# ECU.net
KiCad netlist of a schematic drawn in EAGLE
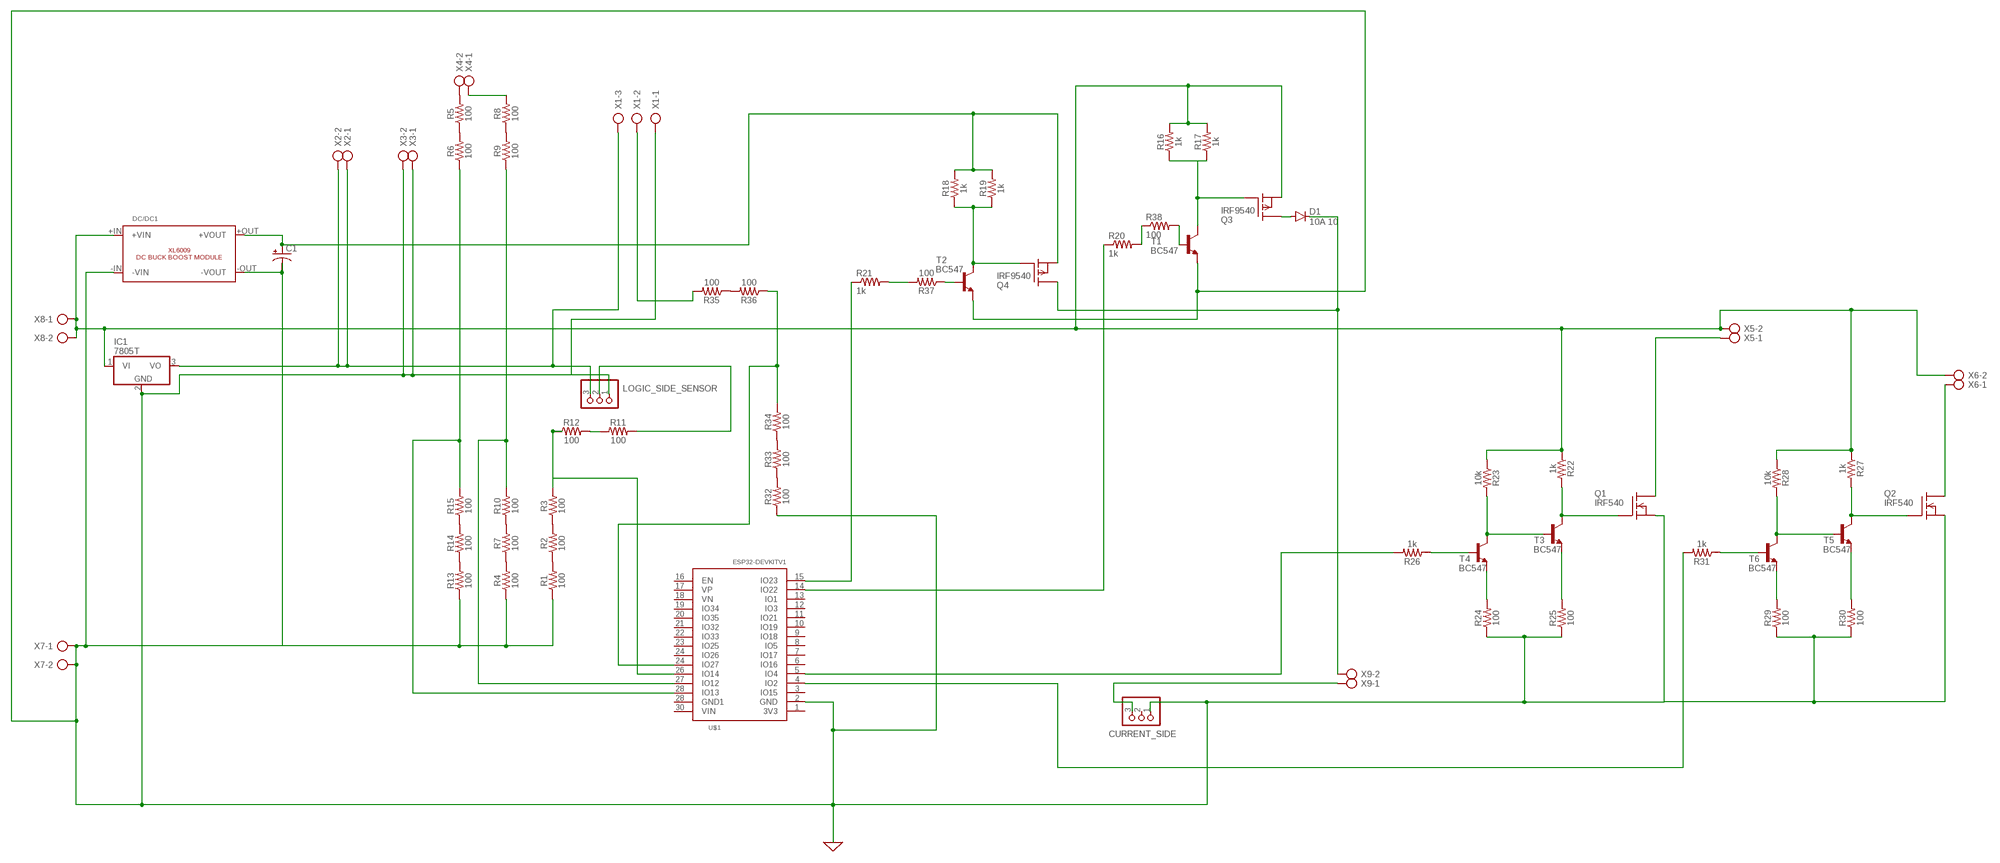
[diagram p0: schematic, sheet 1]

(export (version "E")
  (design (tool "Eeschema 10.0.6"))
  (components
    (comp (ref "C1")
      (value "CPOL-USE7.5-18")
      (footprint "eagle-import:E7,5-18")
      (libsource (lib "eagle-import") (part "CPOL-USE7.5-18"))
    )
    (comp (ref "CURRENT_SIDE")
      (value "PINHD-1X3")
      (footprint "eagle-import:1X03")
      (libsource (lib "eagle-import") (part "PINHD-1X3"))
    )
    (comp (ref "D1")
      (value "10A 10")
      (footprint "eagle-import:DO201-15")
      (libsource (lib "eagle-import") (part "1N5400"))
    )
    (comp (ref "DC/DC1")
      (value "XL6009_DC_BUCK_BOOST_MODULE")
      (footprint "eagle-import:XL6009_DC_BUCK_BOOST_MODULE")
      (libsource (lib "eagle-import") (part "XL6009_DC_BUCK_BOOST_MODULE"))
    )
    (comp (ref "IC1")
      (value "7805T")
      (footprint "eagle-import:TO220H")
      (libsource (lib "eagle-import") (part "78T05"))
    )
    (comp (ref "LOGIC_SIDE_SENSOR")
      (value "PINHD-1X3")
      (footprint "eagle-import:1X03")
      (libsource (lib "eagle-import") (part "PINHD-1X3"))
    )
    (comp (ref "Q1")
      (value "IRF540")
      (footprint "eagle-import:TO220")
      (libsource (lib "eagle-import") (part "IRF540"))
    )
    (comp (ref "Q2")
      (value "IRF540")
      (footprint "eagle-import:TO220")
      (libsource (lib "eagle-import") (part "IRF540"))
    )
    (comp (ref "Q3")
      (value "IRF9540")
      (footprint "eagle-import:TO220")
      (libsource (lib "eagle-import") (part "IRF9530"))
    )
    (comp (ref "Q4")
      (value "IRF9540")
      (footprint "eagle-import:TO220")
      (libsource (lib "eagle-import") (part "IRF9530"))
    )
    (comp (ref "R1")
      (value "100")
      (footprint "eagle-import:AXIAL-0.3")
      (libsource (lib "eagle-import") (part "10OHM-HORIZ-1/4W-1%"))
    )
    (comp (ref "R2")
      (value "100")
      (footprint "eagle-import:AXIAL-0.3")
      (libsource (lib "eagle-import") (part "10OHM-HORIZ-1/4W-1%"))
    )
    (comp (ref "R3")
      (value "100")
      (footprint "eagle-import:AXIAL-0.3")
      (libsource (lib "eagle-import") (part "10OHM-HORIZ-1/4W-1%"))
    )
    (comp (ref "R4")
      (value "100")
      (footprint "eagle-import:AXIAL-0.3")
      (libsource (lib "eagle-import") (part "10OHM-HORIZ-1/4W-1%"))
    )
    (comp (ref "R5")
      (value "100")
      (footprint "eagle-import:AXIAL-0.3")
      (libsource (lib "eagle-import") (part "10OHM-HORIZ-1/4W-1%"))
    )
    (comp (ref "R6")
      (value "100")
      (footprint "eagle-import:AXIAL-0.3")
      (libsource (lib "eagle-import") (part "10OHM-HORIZ-1/4W-1%"))
    )
    (comp (ref "R7")
      (value "100")
      (footprint "eagle-import:AXIAL-0.3")
      (libsource (lib "eagle-import") (part "10OHM-HORIZ-1/4W-1%"))
    )
    (comp (ref "R8")
      (value "100")
      (footprint "eagle-import:AXIAL-0.3")
      (libsource (lib "eagle-import") (part "10OHM-HORIZ-1/4W-1%"))
    )
    (comp (ref "R9")
      (value "100")
      (footprint "eagle-import:AXIAL-0.3")
      (libsource (lib "eagle-import") (part "10OHM-HORIZ-1/4W-1%"))
    )
    (comp (ref "R10")
      (value "100")
      (footprint "eagle-import:AXIAL-0.3")
      (libsource (lib "eagle-import") (part "10OHM-HORIZ-1/4W-1%"))
    )
    (comp (ref "R11")
      (value "100")
      (footprint "eagle-import:AXIAL-0.3")
      (libsource (lib "eagle-import") (part "10OHM-HORIZ-1/4W-1%"))
    )
    (comp (ref "R12")
      (value "100")
      (footprint "eagle-import:AXIAL-0.3")
      (libsource (lib "eagle-import") (part "10OHM-HORIZ-1/4W-1%"))
    )
    (comp (ref "R13")
      (value "100")
      (footprint "eagle-import:AXIAL-0.3")
      (libsource (lib "eagle-import") (part "10OHM-HORIZ-1/4W-1%"))
    )
    (comp (ref "R14")
      (value "100")
      (footprint "eagle-import:AXIAL-0.3")
      (libsource (lib "eagle-import") (part "10OHM-HORIZ-1/4W-1%"))
    )
    (comp (ref "R15")
      (value "100")
      (footprint "eagle-import:AXIAL-0.3")
      (libsource (lib "eagle-import") (part "10OHM-HORIZ-1/4W-1%"))
    )
    (comp (ref "R16")
      (value "1k")
      (footprint "eagle-import:AXIAL-0.3")
      (libsource (lib "eagle-import") (part "1KOHM-HORIZ-1/4W-1%"))
    )
    (comp (ref "R17")
      (value "1k")
      (footprint "eagle-import:AXIAL-0.3")
      (libsource (lib "eagle-import") (part "1KOHM-HORIZ-1/4W-1%"))
    )
    (comp (ref "R18")
      (value "1k")
      (footprint "eagle-import:AXIAL-0.3")
      (libsource (lib "eagle-import") (part "1KOHM-HORIZ-1/4W-1%"))
    )
    (comp (ref "R19")
      (value "1k")
      (footprint "eagle-import:AXIAL-0.3")
      (libsource (lib "eagle-import") (part "1KOHM-HORIZ-1/4W-1%"))
    )
    (comp (ref "R20")
      (value "1k")
      (footprint "eagle-import:0207_12")
      (libsource (lib "eagle-import") (part "R-US_0207/12"))
    )
    (comp (ref "R21")
      (value "1k")
      (footprint "eagle-import:0207_12")
      (libsource (lib "eagle-import") (part "R-US_0207/12"))
    )
    (comp (ref "R22")
      (value "1k")
      (footprint "eagle-import:AXIAL-0.3")
      (libsource (lib "eagle-import") (part "1KOHM-HORIZ-1/4W-1%"))
    )
    (comp (ref "R23")
      (value "10k")
      (footprint "eagle-import:AXIAL-0.3")
      (libsource (lib "eagle-import") (part "1KOHM-HORIZ-1/4W-1%"))
    )
    (comp (ref "R24")
      (value "100")
      (footprint "eagle-import:AXIAL-0.3")
      (libsource (lib "eagle-import") (part "10OHM-HORIZ-1/4W-1%"))
    )
    (comp (ref "R25")
      (value "100")
      (footprint "eagle-import:AXIAL-0.3")
      (libsource (lib "eagle-import") (part "10OHM-HORIZ-1/4W-1%"))
    )
    (comp (ref "R26")
      (value "1k")
      (footprint "eagle-import:AXIAL-0.3")
      (libsource (lib "eagle-import") (part "1KOHM-HORIZ-1/4W-1%"))
    )
    (comp (ref "R27")
      (value "1k")
      (footprint "eagle-import:AXIAL-0.3")
      (libsource (lib "eagle-import") (part "1KOHM-HORIZ-1/4W-1%"))
    )
    (comp (ref "R28")
      (value "10k")
      (footprint "eagle-import:AXIAL-0.3")
      (libsource (lib "eagle-import") (part "1KOHM-HORIZ-1/4W-1%"))
    )
    (comp (ref "R29")
      (value "100")
      (footprint "eagle-import:AXIAL-0.3")
      (libsource (lib "eagle-import") (part "10OHM-HORIZ-1/4W-1%"))
    )
    (comp (ref "R30")
      (value "100")
      (footprint "eagle-import:AXIAL-0.3")
      (libsource (lib "eagle-import") (part "10OHM-HORIZ-1/4W-1%"))
    )
    (comp (ref "R31")
      (value "1k")
      (footprint "eagle-import:AXIAL-0.3")
      (libsource (lib "eagle-import") (part "1KOHM-HORIZ-1/4W-1%"))
    )
    (comp (ref "R32")
      (value "100")
      (footprint "eagle-import:AXIAL-0.3")
      (libsource (lib "eagle-import") (part "10OHM-HORIZ-1/4W-1%"))
    )
    (comp (ref "R33")
      (value "100")
      (footprint "eagle-import:AXIAL-0.3")
      (libsource (lib "eagle-import") (part "10OHM-HORIZ-1/4W-1%"))
    )
    (comp (ref "R34")
      (value "100")
      (footprint "eagle-import:AXIAL-0.3")
      (libsource (lib "eagle-import") (part "10OHM-HORIZ-1/4W-1%"))
    )
    (comp (ref "R35")
      (value "100")
      (footprint "eagle-import:AXIAL-0.3")
      (libsource (lib "eagle-import") (part "10OHM-HORIZ-1/4W-1%"))
    )
    (comp (ref "R36")
      (value "100")
      (footprint "eagle-import:AXIAL-0.3")
      (libsource (lib "eagle-import") (part "10OHM-HORIZ-1/4W-1%"))
    )
    (comp (ref "R37")
      (value "100")
      (footprint "eagle-import:AXIAL-0.3")
      (libsource (lib "eagle-import") (part "10OHM-HORIZ-1/4W-1%"))
    )
    (comp (ref "R38")
      (value "100")
      (footprint "eagle-import:0207_12")
      (libsource (lib "eagle-import") (part "R-US_0207/12"))
    )
    (comp (ref "T1")
      (value "BC547")
      (footprint "eagle-import:TO92")
      (libsource (lib "eagle-import") (part "BC547"))
    )
    (comp (ref "T2")
      (value "BC547")
      (footprint "eagle-import:TO92")
      (libsource (lib "eagle-import") (part "BC547"))
    )
    (comp (ref "T3")
      (value "BC547")
      (footprint "eagle-import:TO92")
      (libsource (lib "eagle-import") (part "BC547"))
    )
    (comp (ref "T4")
      (value "BC547")
      (footprint "eagle-import:TO92")
      (libsource (lib "eagle-import") (part "BC547"))
    )
    (comp (ref "T5")
      (value "BC547")
      (footprint "eagle-import:TO92")
      (libsource (lib "eagle-import") (part "BC547"))
    )
    (comp (ref "T6")
      (value "BC547")
      (footprint "eagle-import:TO92")
      (libsource (lib "eagle-import") (part "BC547"))
    )
    (comp (ref "U$1")
      (value "ESP32DEVKITV1")
      (footprint "eagle-import:ESP32-DEVKITV1")
      (libsource (lib "eagle-import") (part "ESP32DEVKITV1"))
    )
    (comp (ref "X1")
      (value "AK300/3")
      (footprint "eagle-import:AK300_3")
      (libsource (lib "eagle-import") (part "AK300/3"))
    )
    (comp (ref "X2")
      (value "AK300/2")
      (footprint "eagle-import:AK300_2")
      (libsource (lib "eagle-import") (part "AK300/2"))
    )
    (comp (ref "X3")
      (value "AK300/2")
      (footprint "eagle-import:AK300_2")
      (libsource (lib "eagle-import") (part "AK300/2"))
    )
    (comp (ref "X4")
      (value "AK300/2")
      (footprint "eagle-import:AK300_2")
      (libsource (lib "eagle-import") (part "AK300/2"))
    )
    (comp (ref "X5")
      (value "AK300/2")
      (footprint "eagle-import:AK300_2")
      (libsource (lib "eagle-import") (part "AK300/2"))
    )
    (comp (ref "X6")
      (value "AK300/2")
      (footprint "eagle-import:AK300_2")
      (libsource (lib "eagle-import") (part "AK300/2"))
    )
    (comp (ref "X7")
      (value "AK300/2")
      (footprint "eagle-import:AK300_2")
      (libsource (lib "eagle-import") (part "AK300/2"))
    )
    (comp (ref "X8")
      (value "AK300/2")
      (footprint "eagle-import:AK300_2")
      (libsource (lib "eagle-import") (part "AK300/2"))
    )
    (comp (ref "X9")
      (value "AK300/2")
      (footprint "eagle-import:AK300_2")
      (libsource (lib "eagle-import") (part "AK300/2"))
    )
  )
  (nets
    (net (code "1") (name "GND") (class "Default")
      (node (ref "C1") (pin "-") (pinfunction "-_-") (pintype "passive"))
      (node (ref "CURRENT_SIDE") (pin "1") (pinfunction "1_1") (pintype "passive"))
      (node (ref "DC/DC1") (pin "-IN") (pinfunction "-VIN_-IN") (pintype "bidirectional"))
      (node (ref "DC/DC1") (pin "-OUT") (pinfunction "-VOUT_-OUT") (pintype "bidirectional"))
      (node (ref "IC1") (pin "2") (pinfunction "GND_2") (pintype "passive"))
      (node (ref "LOGIC_SIDE_SENSOR") (pin "1") (pinfunction "1_1") (pintype "passive"))
      (node (ref "Q1") (pin "3") (pinfunction "S_3") (pintype "passive"))
      (node (ref "Q2") (pin "3") (pinfunction "S_3") (pintype "passive"))
      (node (ref "R1") (pin "P$1") (pinfunction "1_P$1") (pintype "passive"))
      (node (ref "R13") (pin "P$1") (pinfunction "1_P$1") (pintype "passive"))
      (node (ref "R24") (pin "P$1") (pinfunction "1_P$1") (pintype "passive"))
      (node (ref "R25") (pin "P$1") (pinfunction "1_P$1") (pintype "passive"))
      (node (ref "R29") (pin "P$1") (pinfunction "1_P$1") (pintype "passive"))
      (node (ref "R30") (pin "P$1") (pinfunction "1_P$1") (pintype "passive"))
      (node (ref "R32") (pin "P$1") (pinfunction "1_P$1") (pintype "passive"))
      (node (ref "R4") (pin "P$1") (pinfunction "1_P$1") (pintype "passive"))
      (node (ref "T1") (pin "1") (pinfunction "E_1") (pintype "passive"))
      (node (ref "T2") (pin "1") (pinfunction "E_1") (pintype "passive"))
      (node (ref "U$1") (pin "2") (pinfunction "GND_2") (pintype "bidirectional"))
      (node (ref "X1") (pin "1") (pinfunction "KL_1") (pintype "passive"))
      (node (ref "X3") (pin "1") (pinfunction "KL_1") (pintype "passive"))
      (node (ref "X3") (pin "2") (pinfunction "KL_2") (pintype "passive"))
      (node (ref "X7") (pin "1") (pinfunction "KL_1") (pintype "passive"))
      (node (ref "X7") (pin "2") (pinfunction "KL_2") (pintype "passive"))
    )
    (net (code "2") (name "Net-(DC/DC1-+VIN)") (class "Default")
      (node (ref "DC/DC1") (pin "+IN") (pinfunction "+VIN_+IN") (pintype "bidirectional"))
      (node (ref "IC1") (pin "1") (pinfunction "VI_1") (pintype "input"))
      (node (ref "Q3") (pin "3") (pinfunction "S_3") (pintype "passive"))
      (node (ref "R16") (pin "P$2") (pinfunction "2_P$2") (pintype "passive"))
      (node (ref "R17") (pin "P$2") (pinfunction "2_P$2") (pintype "passive"))
      (node (ref "R22") (pin "P$1") (pinfunction "1_P$1") (pintype "passive"))
      (node (ref "R23") (pin "P$1") (pinfunction "1_P$1") (pintype "passive"))
      (node (ref "R27") (pin "P$1") (pinfunction "1_P$1") (pintype "passive"))
      (node (ref "R28") (pin "P$1") (pinfunction "1_P$1") (pintype "passive"))
      (node (ref "X5") (pin "2") (pinfunction "KL_2") (pintype "passive"))
      (node (ref "X6") (pin "2") (pinfunction "KL_2") (pintype "passive"))
      (node (ref "X8") (pin "1") (pinfunction "KL_1") (pintype "passive"))
      (node (ref "X8") (pin "2") (pinfunction "KL_2") (pintype "passive"))
    )
    (net (code "3") (name "Net-(DC/DC1-+VOUT)") (class "Default")
      (node (ref "C1") (pin "+") (pinfunction "+_+") (pintype "passive"))
      (node (ref "DC/DC1") (pin "+OUT") (pinfunction "+VOUT_+OUT") (pintype "bidirectional"))
      (node (ref "Q4") (pin "3") (pinfunction "S_3") (pintype "passive"))
      (node (ref "R18") (pin "P$2") (pinfunction "2_P$2") (pintype "passive"))
      (node (ref "R19") (pin "P$2") (pinfunction "2_P$2") (pintype "passive"))
    )
    (net (code "4") (name "Net-(IC1-VO)") (class "Default")
      (node (ref "IC1") (pin "3") (pinfunction "VO_3") (pintype "passive"))
      (node (ref "LOGIC_SIDE_SENSOR") (pin "3") (pinfunction "3_3") (pintype "passive"))
      (node (ref "X1") (pin "3") (pinfunction "KL_3") (pintype "passive"))
      (node (ref "X2") (pin "1") (pinfunction "KL_1") (pintype "passive"))
      (node (ref "X2") (pin "2") (pinfunction "KL_2") (pintype "passive"))
    )
    (net (code "5") (name "Net-(Q1-D)") (class "Default")
      (node (ref "Q1") (pin "2") (pinfunction "D_2") (pintype "passive"))
      (node (ref "X5") (pin "1") (pinfunction "KL_1") (pintype "passive"))
    )
    (net (code "6") (name "Net-(Q1-G)") (class "Default")
      (node (ref "Q1") (pin "1") (pinfunction "G_1") (pintype "passive"))
      (node (ref "R22") (pin "P$2") (pinfunction "2_P$2") (pintype "passive"))
      (node (ref "T3") (pin "3") (pinfunction "C_3") (pintype "passive"))
    )
    (net (code "7") (name "Net-(Q2-D)") (class "Default")
      (node (ref "Q2") (pin "2") (pinfunction "D_2") (pintype "passive"))
      (node (ref "X6") (pin "1") (pinfunction "KL_1") (pintype "passive"))
    )
    (net (code "8") (name "Net-(Q2-G)") (class "Default")
      (node (ref "Q2") (pin "1") (pinfunction "G_1") (pintype "passive"))
      (node (ref "R27") (pin "P$2") (pinfunction "2_P$2") (pintype "passive"))
      (node (ref "T5") (pin "3") (pinfunction "C_3") (pintype "passive"))
    )
    (net (code "9") (name "Net-(Q3-D)") (class "Default")
      (node (ref "D1") (pin "A") (pinfunction "A_A") (pintype "passive"))
      (node (ref "Q3") (pin "2") (pinfunction "D_2") (pintype "passive"))
    )
    (net (code "10") (name "Net-(Q3-G)") (class "Default")
      (node (ref "Q3") (pin "1") (pinfunction "G_1") (pintype "passive"))
      (node (ref "R16") (pin "P$1") (pinfunction "1_P$1") (pintype "passive"))
      (node (ref "R17") (pin "P$1") (pinfunction "1_P$1") (pintype "passive"))
      (node (ref "T1") (pin "3") (pinfunction "C_3") (pintype "passive"))
    )
    (net (code "11") (name "Net-(Q4-D)") (class "Default")
      (node (ref "D1") (pin "C") (pinfunction "C_C") (pintype "passive"))
      (node (ref "Q4") (pin "2") (pinfunction "D_2") (pintype "passive"))
      (node (ref "X9") (pin "2") (pinfunction "KL_2") (pintype "passive"))
    )
    (net (code "12") (name "Net-(Q4-G)") (class "Default")
      (node (ref "Q4") (pin "1") (pinfunction "G_1") (pintype "passive"))
      (node (ref "R18") (pin "P$1") (pinfunction "1_P$1") (pintype "passive"))
      (node (ref "R19") (pin "P$1") (pinfunction "1_P$1") (pintype "passive"))
      (node (ref "T2") (pin "3") (pinfunction "C_3") (pintype "passive"))
    )
    (net (code "13") (name "Net-(R1-2)") (class "Default")
      (node (ref "R1") (pin "P$2") (pinfunction "2_P$2") (pintype "passive"))
      (node (ref "R2") (pin "P$1") (pinfunction "1_P$1") (pintype "passive"))
    )
    (net (code "14") (name "Net-(R2-2)") (class "Default")
      (node (ref "R2") (pin "P$2") (pinfunction "2_P$2") (pintype "passive"))
      (node (ref "R3") (pin "P$1") (pinfunction "1_P$1") (pintype "passive"))
    )
    (net (code "15") (name "Net-(R4-2)") (class "Default")
      (node (ref "R4") (pin "P$2") (pinfunction "2_P$2") (pintype "passive"))
      (node (ref "R7") (pin "P$1") (pinfunction "1_P$1") (pintype "passive"))
    )
    (net (code "16") (name "Net-(R5-1)") (class "Default")
      (node (ref "R5") (pin "P$1") (pinfunction "1_P$1") (pintype "passive"))
      (node (ref "R6") (pin "P$2") (pinfunction "2_P$2") (pintype "passive"))
    )
    (net (code "17") (name "Net-(R5-2)") (class "Default")
      (node (ref "R5") (pin "P$2") (pinfunction "2_P$2") (pintype "passive"))
      (node (ref "X4") (pin "2") (pinfunction "KL_2") (pintype "passive"))
    )
    (net (code "18") (name "Net-(R8-1)") (class "Default")
      (node (ref "R8") (pin "P$1") (pinfunction "1_P$1") (pintype "passive"))
      (node (ref "R9") (pin "P$2") (pinfunction "2_P$2") (pintype "passive"))
    )
    (net (code "19") (name "Net-(R8-2)") (class "Default")
      (node (ref "R8") (pin "P$2") (pinfunction "2_P$2") (pintype "passive"))
      (node (ref "X4") (pin "1") (pinfunction "KL_1") (pintype "passive"))
    )
    (net (code "20") (name "Net-(R10-1)") (class "Default")
      (node (ref "R10") (pin "P$1") (pinfunction "1_P$1") (pintype "passive"))
      (node (ref "R7") (pin "P$2") (pinfunction "2_P$2") (pintype "passive"))
    )
    (net (code "21") (name "Net-(R10-2)") (class "Default")
      (node (ref "R10") (pin "P$2") (pinfunction "2_P$2") (pintype "passive"))
      (node (ref "R9") (pin "P$1") (pinfunction "1_P$1") (pintype "passive"))
      (node (ref "U$1") (pin "27") (pinfunction "IO12_27") (pintype "bidirectional"))
    )
    (net (code "22") (name "Net-(R11-1)") (class "Default")
      (node (ref "R11") (pin "P$1") (pinfunction "1_P$1") (pintype "passive"))
      (node (ref "R12") (pin "P$2") (pinfunction "2_P$2") (pintype "passive"))
    )
    (net (code "23") (name "Net-(R11-2)") (class "Default")
      (node (ref "LOGIC_SIDE_SENSOR") (pin "2") (pinfunction "2_2") (pintype "passive"))
      (node (ref "R11") (pin "P$2") (pinfunction "2_P$2") (pintype "passive"))
    )
    (net (code "24") (name "Net-(R12-1)") (class "Default")
      (node (ref "R12") (pin "P$1") (pinfunction "1_P$1") (pintype "passive"))
      (node (ref "R3") (pin "P$2") (pinfunction "2_P$2") (pintype "passive"))
      (node (ref "U$1") (pin "26") (pinfunction "IO14_26") (pintype "bidirectional"))
    )
    (net (code "25") (name "Net-(R13-2)") (class "Default")
      (node (ref "R13") (pin "P$2") (pinfunction "2_P$2") (pintype "passive"))
      (node (ref "R14") (pin "P$1") (pinfunction "1_P$1") (pintype "passive"))
    )
    (net (code "26") (name "Net-(R14-2)") (class "Default")
      (node (ref "R14") (pin "P$2") (pinfunction "2_P$2") (pintype "passive"))
      (node (ref "R15") (pin "P$1") (pinfunction "1_P$1") (pintype "passive"))
    )
    (net (code "27") (name "Net-(R15-2)") (class "Default")
      (node (ref "R15") (pin "P$2") (pinfunction "2_P$2") (pintype "passive"))
      (node (ref "R6") (pin "P$1") (pinfunction "1_P$1") (pintype "passive"))
      (node (ref "U$1") (pin "28") (pinfunction "IO13_28") (pintype "bidirectional"))
    )
    (net (code "28") (name "Net-(R20-Pad2)") (class "Default")
      (node (ref "R20") (pin "2") (pinfunction "2_2") (pintype "passive"))
      (node (ref "R38") (pin "1") (pinfunction "1_1") (pintype "passive"))
    )
    (net (code "29") (name "Net-(R23-2)") (class "Default")
      (node (ref "R23") (pin "P$2") (pinfunction "2_P$2") (pintype "passive"))
      (node (ref "T3") (pin "2") (pinfunction "B_2") (pintype "passive"))
      (node (ref "T4") (pin "3") (pinfunction "C_3") (pintype "passive"))
    )
    (net (code "30") (name "Net-(R24-2)") (class "Default")
      (node (ref "R24") (pin "P$2") (pinfunction "2_P$2") (pintype "passive"))
      (node (ref "T4") (pin "1") (pinfunction "E_1") (pintype "passive"))
    )
    (net (code "31") (name "Net-(R25-2)") (class "Default")
      (node (ref "R25") (pin "P$2") (pinfunction "2_P$2") (pintype "passive"))
      (node (ref "T3") (pin "1") (pinfunction "E_1") (pintype "passive"))
    )
    (net (code "32") (name "Net-(R26-1)") (class "Default")
      (node (ref "R26") (pin "P$1") (pinfunction "1_P$1") (pintype "passive"))
      (node (ref "T4") (pin "2") (pinfunction "B_2") (pintype "passive"))
    )
    (net (code "33") (name "Net-(R26-2)") (class "Default")
      (node (ref "R26") (pin "P$2") (pinfunction "2_P$2") (pintype "passive"))
      (node (ref "U$1") (pin "5") (pinfunction "IO4_5") (pintype "bidirectional"))
    )
    (net (code "34") (name "Net-(R28-2)") (class "Default")
      (node (ref "R28") (pin "P$2") (pinfunction "2_P$2") (pintype "passive"))
      (node (ref "T5") (pin "2") (pinfunction "B_2") (pintype "passive"))
      (node (ref "T6") (pin "3") (pinfunction "C_3") (pintype "passive"))
    )
    (net (code "35") (name "Net-(R29-2)") (class "Default")
      (node (ref "R29") (pin "P$2") (pinfunction "2_P$2") (pintype "passive"))
      (node (ref "T6") (pin "1") (pinfunction "E_1") (pintype "passive"))
    )
    (net (code "36") (name "Net-(R30-2)") (class "Default")
      (node (ref "R30") (pin "P$2") (pinfunction "2_P$2") (pintype "passive"))
      (node (ref "T5") (pin "1") (pinfunction "E_1") (pintype "passive"))
    )
    (net (code "37") (name "Net-(R31-1)") (class "Default")
      (node (ref "R31") (pin "P$1") (pinfunction "1_P$1") (pintype "passive"))
      (node (ref "T6") (pin "2") (pinfunction "B_2") (pintype "passive"))
    )
    (net (code "38") (name "Net-(R31-2)") (class "Default")
      (node (ref "R31") (pin "P$2") (pinfunction "2_P$2") (pintype "passive"))
      (node (ref "U$1") (pin "4") (pinfunction "IO2_4") (pintype "bidirectional"))
    )
    (net (code "39") (name "Net-(R32-2)") (class "Default")
      (node (ref "R32") (pin "P$2") (pinfunction "2_P$2") (pintype "passive"))
      (node (ref "R33") (pin "P$1") (pinfunction "1_P$1") (pintype "passive"))
    )
    (net (code "40") (name "Net-(R33-2)") (class "Default")
      (node (ref "R33") (pin "P$2") (pinfunction "2_P$2") (pintype "passive"))
      (node (ref "R34") (pin "P$1") (pinfunction "1_P$1") (pintype "passive"))
    )
    (net (code "41") (name "Net-(R34-2)") (class "Default")
      (node (ref "R34") (pin "P$2") (pinfunction "2_P$2") (pintype "passive"))
      (node (ref "R36") (pin "P$1") (pinfunction "1_P$1") (pintype "passive"))
      (node (ref "U$1") (pin "24") (pinfunction "IO27_24") (pintype "bidirectional"))
    )
    (net (code "42") (name "Net-(R35-1)") (class "Default")
      (node (ref "R35") (pin "P$1") (pinfunction "1_P$1") (pintype "passive"))
      (node (ref "R36") (pin "P$2") (pinfunction "2_P$2") (pintype "passive"))
    )
    (net (code "43") (name "Net-(R35-2)") (class "Default")
      (node (ref "R35") (pin "P$2") (pinfunction "2_P$2") (pintype "passive"))
      (node (ref "X1") (pin "2") (pinfunction "KL_2") (pintype "passive"))
    )
    (net (code "44") (name "Net-(R37-1)") (class "Default")
      (node (ref "R37") (pin "P$1") (pinfunction "1_P$1") (pintype "passive"))
      (node (ref "T2") (pin "2") (pinfunction "B_2") (pintype "passive"))
    )
    (net (code "45") (name "Net-(R37-2)") (class "Default")
      (node (ref "R21") (pin "2") (pinfunction "2_2") (pintype "passive"))
      (node (ref "R37") (pin "P$2") (pinfunction "2_P$2") (pintype "passive"))
    )
    (net (code "46") (name "Net-(T1-B)") (class "Default")
      (node (ref "R38") (pin "2") (pinfunction "2_2") (pintype "passive"))
      (node (ref "T1") (pin "2") (pinfunction "B_2") (pintype "passive"))
    )
    (net (code "47") (name "Net-(U$1-IO22)") (class "Default")
      (node (ref "R20") (pin "1") (pinfunction "1_1") (pintype "passive"))
      (node (ref "U$1") (pin "14") (pinfunction "IO22_14") (pintype "bidirectional"))
    )
    (net (code "48") (name "Net-(U$1-IO23)") (class "Default")
      (node (ref "R21") (pin "1") (pinfunction "1_1") (pintype "passive"))
      (node (ref "U$1") (pin "15") (pinfunction "IO23_15") (pintype "bidirectional"))
    )
    (net (code "49") (name "Net-(X9A-KL)") (class "Default")
      (node (ref "CURRENT_SIDE") (pin "3") (pinfunction "3_3") (pintype "passive"))
      (node (ref "X9") (pin "1") (pinfunction "KL_1") (pintype "passive"))
    )
    (net (code "50") (name "unconnected-(CURRENT_SIDE-Pad2)") (class "Default")
      (node (ref "CURRENT_SIDE") (pin "2") (pinfunction "2_2") (pintype "passive"))
    )
    (net (code "51") (name "unconnected-(U$1-3V3-Pad1)") (class "Default")
      (node (ref "U$1") (pin "1") (pinfunction "3V3_1") (pintype "bidirectional"))
    )
    (net (code "52") (name "unconnected-(U$1-EN-Pad16)") (class "Default")
      (node (ref "U$1") (pin "16") (pinfunction "EN_16") (pintype "bidirectional"))
    )
    (net (code "53") (name "unconnected-(U$1-GND1-Pad28)") (class "Default")
      (node (ref "U$1") (pin "28") (pinfunction "GND1_28") (pintype "bidirectional"))
    )
    (net (code "54") (name "unconnected-(U$1-IO1-Pad13)") (class "Default")
      (node (ref "U$1") (pin "13") (pinfunction "IO1_13") (pintype "bidirectional"))
    )
    (net (code "55") (name "unconnected-(U$1-IO3-Pad12)") (class "Default")
      (node (ref "U$1") (pin "12") (pinfunction "IO3_12") (pintype "bidirectional"))
    )
    (net (code "56") (name "unconnected-(U$1-IO5-Pad8)") (class "Default")
      (node (ref "U$1") (pin "8") (pinfunction "IO5_8") (pintype "bidirectional"))
    )
    (net (code "57") (name "unconnected-(U$1-IO15-Pad3)") (class "Default")
      (node (ref "U$1") (pin "3") (pinfunction "IO15_3") (pintype "bidirectional"))
    )
    (net (code "58") (name "unconnected-(U$1-IO16-Pad6)") (class "Default")
      (node (ref "U$1") (pin "6") (pinfunction "IO16_6") (pintype "bidirectional"))
    )
    (net (code "59") (name "unconnected-(U$1-IO17-Pad7)") (class "Default")
      (node (ref "U$1") (pin "7") (pinfunction "IO17_7") (pintype "bidirectional"))
    )
    (net (code "60") (name "unconnected-(U$1-IO18-Pad9)") (class "Default")
      (node (ref "U$1") (pin "9") (pinfunction "IO18_9") (pintype "bidirectional"))
    )
    (net (code "61") (name "unconnected-(U$1-IO19-Pad10)") (class "Default")
      (node (ref "U$1") (pin "10") (pinfunction "IO19_10") (pintype "bidirectional"))
    )
    (net (code "62") (name "unconnected-(U$1-IO21-Pad11)") (class "Default")
      (node (ref "U$1") (pin "11") (pinfunction "IO21_11") (pintype "bidirectional"))
    )
    (net (code "63") (name "unconnected-(U$1-IO25-Pad23)") (class "Default")
      (node (ref "U$1") (pin "23") (pinfunction "IO25_23") (pintype "bidirectional"))
    )
    (net (code "64") (name "unconnected-(U$1-IO26-Pad24)") (class "Default")
      (node (ref "U$1") (pin "24") (pinfunction "IO26_24") (pintype "bidirectional"))
    )
    (net (code "65") (name "unconnected-(U$1-IO32-Pad21)") (class "Default")
      (node (ref "U$1") (pin "21") (pinfunction "IO32_21") (pintype "bidirectional"))
    )
    (net (code "66") (name "unconnected-(U$1-IO33-Pad22)") (class "Default")
      (node (ref "U$1") (pin "22") (pinfunction "IO33_22") (pintype "bidirectional"))
    )
    (net (code "67") (name "unconnected-(U$1-IO34-Pad19)") (class "Default")
      (node (ref "U$1") (pin "19") (pinfunction "IO34_19") (pintype "bidirectional"))
    )
    (net (code "68") (name "unconnected-(U$1-IO35-Pad20)") (class "Default")
      (node (ref "U$1") (pin "20") (pinfunction "IO35_20") (pintype "bidirectional"))
    )
    (net (code "69") (name "unconnected-(U$1-VIN-Pad30)") (class "Default")
      (node (ref "U$1") (pin "30") (pinfunction "VIN_30") (pintype "bidirectional"))
    )
    (net (code "70") (name "unconnected-(U$1-VN-Pad18)") (class "Default")
      (node (ref "U$1") (pin "18") (pinfunction "VN_18") (pintype "bidirectional"))
    )
    (net (code "71") (name "unconnected-(U$1-VP-Pad17)") (class "Default")
      (node (ref "U$1") (pin "17") (pinfunction "VP_17") (pintype "bidirectional"))
    )
  )
)
